# IR_CURRENT_SENSE.net
KiCad netlist of a schematic drawn in Altium Designer
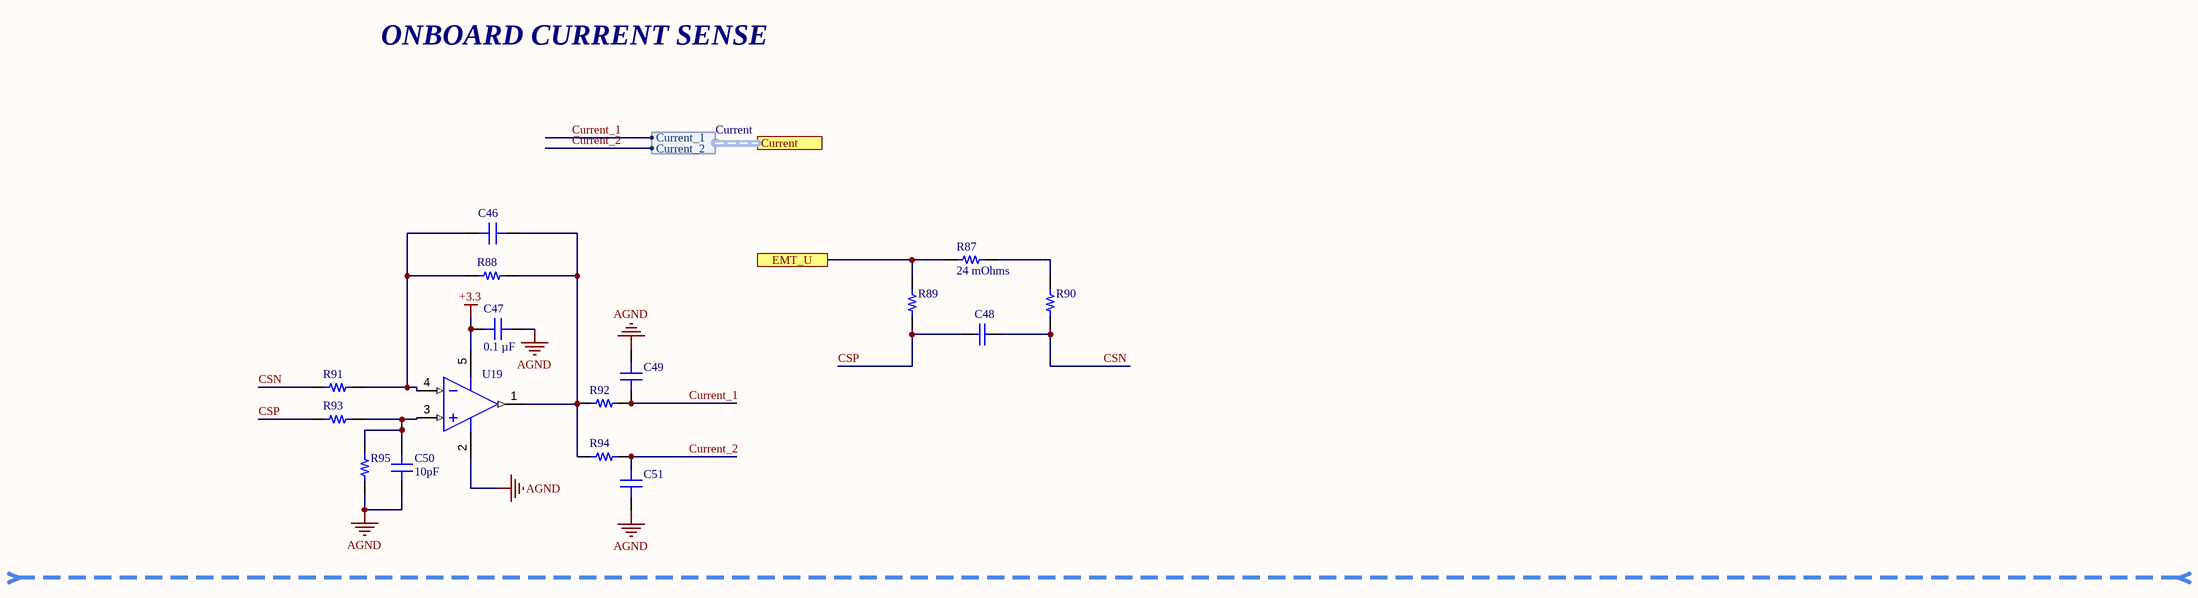
[diagram p0: IR_CURRENT_SENSE.SchDoc]

(export (version "E")
  (design (tool "Eeschema 10.0.6"))
  (components
    (comp (ref "C46")
      (value "10pF")
      (footprint "CAP 0402_1005")
      (description "CAP CER 10PF 50V C0G/NP0 0402")
      (fields (field (name "PART NUMBER") "04025U100JAT2A") (field (name "MANUFACTURER") "AVX Corporation"))
      (libsource (lib "Celestial Altium Library - altium_library") (part "Capacitor"))
    )
    (comp (ref "C47")
      (value "0.1 µF")
      (footprint "CAP 0402_1005")
      (description "CAP CER 0402 0.1UF 16V X7R 10%")
      (fields (field (name "PART NUMBER") "C0402C104K4RECAUTO") (field (name "MANUFACTURER") "KEMET"))
      (libsource (lib "Celestial Altium Library - altium_library") (part "Capacitor"))
    )
    (comp (ref "C48")
      (value "GRM155R71H102KA01D")
      (footprint "CAPC1005X55X25ML5T10")
      (description "Chip Capacitor, 1 nF, +/- 10%, 50 V, -55 to 125 degC, 0402 (1005 Metric), RoHS, Tape and Reel")
      (fields (field (name "TOLERANCE") "10%"))
      (libsource (lib "Altium Content Vault") (part "CAP-NP-2"))
    )
    (comp (ref "C49")
      (value "1000 pF")
      (footprint "CAP 0402_1005")
      (description "CAP CER 1000PF 50V NP0 0402")
      (fields (field (name "PART NUMBER") "UMK105CG102JVHF") (field (name "MANUFACTURER") "Taiyo Yuden"))
      (libsource (lib "Celestial Altium Library - altium_library") (part "Capacitor"))
    )
    (comp (ref "C50")
      (value "10pF")
      (footprint "CAP 0402_1005")
      (description "CAP CER 10PF 50V C0G/NP0 0402")
      (fields (field (name "PART NUMBER") "04025U100JAT2A") (field (name "MANUFACTURER") "AVX Corporation"))
      (libsource (lib "Celestial Altium Library - altium_library") (part "Capacitor"))
    )
    (comp (ref "C51")
      (value "1000 pF")
      (footprint "CAP 0402_1005")
      (description "CAP CER 1000PF 50V NP0 0402")
      (fields (field (name "PART NUMBER") "UMK105CG102JVHF") (field (name "MANUFACTURER") "Taiyo Yuden"))
      (libsource (lib "Celestial Altium Library - altium_library") (part "Capacitor"))
    )
    (comp (ref "R87")
      (value "24 mOhms")
      (footprint "STACKPOLE CSR0805")
      (description "RES 0.024 OHM 5% 1/3W 0603")
      (fields
        (field (name "PART NUMBER") "ERJ-3BWJR024V")
        (field (name "MANUFACTURER") "Panasonic Electronic Components")
      )
      (libsource (lib "Celestial Altium Library - altium_library") (part "Resistor"))
    )
    (comp (ref "R88")
      (value "20 kOhms")
      (footprint "RES 0402_1005")
      (description "RES SMD 20K OHM 0.1% 1/16W 0402")
      (fields
        (field (name "PART NUMBER") "CPF0402B20KE")
        (field (name "MANUFACTURER") "TE Connectivity Passive Product")
      )
      (libsource (lib "Celestial Altium Library - altium_library") (part "Resistor"))
    )
    (comp (ref "R89")
      (value "100 mOhms")
      (footprint "STACKPOLE CSR0805")
      (description "RES 0.1 OHM 1% 1/4W 0603")
      (fields (field (name "PART NUMBER") "560050316001") (field (name "MANUFACTURER") "Würth Elektronik"))
      (libsource (lib "Celestial Altium Library - altium_library") (part "Resistor"))
    )
    (comp (ref "R90")
      (value "100 mOhms")
      (footprint "STACKPOLE CSR0805")
      (description "RES 0.1 OHM 1% 1/4W 0603")
      (fields (field (name "PART NUMBER") "560050316001") (field (name "MANUFACTURER") "Würth Elektronik"))
      (libsource (lib "Celestial Altium Library - altium_library") (part "Resistor"))
    )
    (comp (ref "R91")
      (value "249 kOhms")
      (footprint "RES 0402_1005")
      (description "RES 249K OHM 0.1% 1/10W 0402")
      (fields
        (field (name "PART NUMBER") "RP73PF1E249KBTD")
        (field (name "MANUFACTURER") "TE Connectivity Passive Product")
      )
      (libsource (lib "Celestial Altium Library - altium_library") (part "Resistor"))
    )
    (comp (ref "R92")
      (value "100 Ohms")
      (footprint "RES 0402_1005")
      (description "RES 100 OHM 0.5% 1/5W 0402")
      (fields
        (field (name "PART NUMBER") "MCS0402PD1000DE500")
        (field (name "MANUFACTURER") "Vishay Beyschlag")
      )
      (libsource (lib "Celestial Altium Library - altium_library") (part "Resistor"))
    )
    (comp (ref "R93")
      (value "249 kOhms")
      (footprint "RES 0402_1005")
      (description "RES 249K OHM 0.1% 1/10W 0402")
      (fields
        (field (name "PART NUMBER") "RP73PF1E249KBTD")
        (field (name "MANUFACTURER") "TE Connectivity Passive Product")
      )
      (libsource (lib "Celestial Altium Library - altium_library") (part "Resistor"))
    )
    (comp (ref "R94")
      (value "100 Ohms")
      (footprint "RES 0402_1005")
      (description "RES 100 OHM 0.5% 1/5W 0402")
      (fields
        (field (name "PART NUMBER") "MCS0402PD1000DE500")
        (field (name "MANUFACTURER") "Vishay Beyschlag")
      )
      (libsource (lib "Celestial Altium Library - altium_library") (part "Resistor"))
    )
    (comp (ref "R95")
      (value "20 kOhms")
      (footprint "RES 0402_1005")
      (description "RES SMD 20K OHM 0.1% 1/16W 0402")
      (fields
        (field (name "PART NUMBER") "CPF0402B20KE")
        (field (name "MANUFACTURER") "TE Connectivity Passive Product")
      )
      (libsource (lib "Celestial Altium Library - altium_library") (part "Resistor"))
    )
    (comp (ref "U19")
      (value "OPA374AIDBVR")
      (footprint "DBV0005A_M")
      (fields (field (name "MANUFACTURER") "Texas Instruments"))
      (libsource (lib "Altium Content Vault") (part "TI-OPA_SM7XXXX-DBV5"))
    )
  )
  (nets
    (net (code "2") (name "+3.3") (class "Default")
      (node (ref "C47") (pin "1") (pinfunction "1_1") (pintype "passive"))
      (node (ref "U19") (pin "5") (pinfunction "V+_5") (pintype "power_in"))
    )
    (net (code "3") (name "/CSN") (class "Default")
      (node (ref "C48") (pin "2") (pinfunction "2_2") (pintype "passive"))
      (node (ref "R90") (pin "1") (pinfunction "1_1") (pintype "passive"))
      (node (ref "R91") (pin "1") (pinfunction "1_1") (pintype "passive"))
    )
    (net (code "4") (name "/CSP") (class "Default")
      (node (ref "C48") (pin "1") (pinfunction "1_1") (pintype "passive"))
      (node (ref "R89") (pin "1") (pinfunction "1_1") (pintype "passive"))
      (node (ref "R93") (pin "1") (pinfunction "1_1") (pintype "passive"))
    )
    (net (code "5") (name "/Current_1") (class "Default")
      (node (ref "C49") (pin "1") (pinfunction "1_1") (pintype "passive"))
      (node (ref "R92") (pin "2") (pinfunction "2_2") (pintype "passive"))
    )
    (net (code "6") (name "/Current_2") (class "Default")
      (node (ref "C51") (pin "2") (pinfunction "2_2") (pintype "passive"))
      (node (ref "R94") (pin "2") (pinfunction "2_2") (pintype "passive"))
    )
    (net (code "7") (name "/EMT_U") (class "Default")
      (node (ref "R87") (pin "1") (pinfunction "1_1") (pintype "passive"))
      (node (ref "R89") (pin "2") (pinfunction "2_2") (pintype "passive"))
    )
    (net (code "9") (name "AGND") (class "Default")
      (node (ref "C47") (pin "2") (pinfunction "2_2") (pintype "passive"))
      (node (ref "C49") (pin "2") (pinfunction "2_2") (pintype "passive"))
      (node (ref "C50") (pin "2") (pinfunction "2_2") (pintype "passive"))
      (node (ref "C51") (pin "1") (pinfunction "1_1") (pintype "passive"))
      (node (ref "R95") (pin "1") (pinfunction "1_1") (pintype "passive"))
      (node (ref "U19") (pin "2") (pinfunction "V-_2") (pintype "power_in"))
    )
    (net (code "10") (name "Net-(R87-Pad2)") (class "Default")
      (node (ref "R87") (pin "2") (pinfunction "2_2") (pintype "passive"))
      (node (ref "R90") (pin "2") (pinfunction "2_2") (pintype "passive"))
    )
    (net (code "11") (name "Net-(U19-IN+)") (class "Default")
      (node (ref "C50") (pin "1") (pinfunction "1_1") (pintype "passive"))
      (node (ref "R93") (pin "2") (pinfunction "2_2") (pintype "passive"))
      (node (ref "R95") (pin "2") (pinfunction "2_2") (pintype "passive"))
      (node (ref "U19") (pin "3") (pinfunction "IN+_3") (pintype "input"))
    )
    (net (code "12") (name "Net-(U19-IN-)") (class "Default")
      (node (ref "C46") (pin "1") (pinfunction "1_1") (pintype "passive"))
      (node (ref "R88") (pin "1") (pinfunction "1_1") (pintype "passive"))
      (node (ref "R91") (pin "2") (pinfunction "2_2") (pintype "passive"))
      (node (ref "U19") (pin "4") (pinfunction "IN-_4") (pintype "input"))
    )
    (net (code "13") (name "Net-(U19-OUT)") (class "Default")
      (node (ref "C46") (pin "2") (pinfunction "2_2") (pintype "passive"))
      (node (ref "R88") (pin "2") (pinfunction "2_2") (pintype "passive"))
      (node (ref "R92") (pin "1") (pinfunction "1_1") (pintype "passive"))
      (node (ref "R94") (pin "1") (pinfunction "1_1") (pintype "passive"))
      (node (ref "U19") (pin "1") (pinfunction "OUT_1") (pintype "output"))
    )
  )
)
